# POWER.net
KiCad netlist of a schematic drawn in Altium Designer
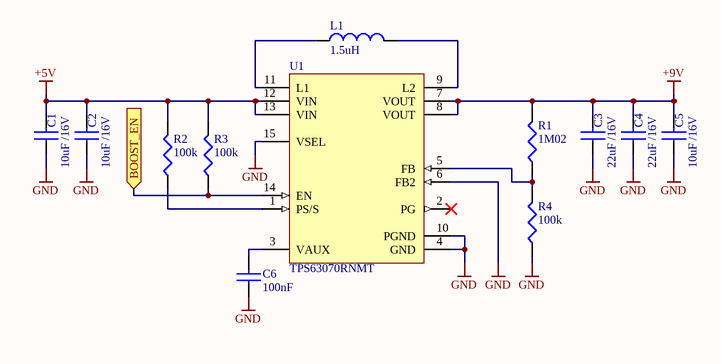
[diagram p0: POWER.SchDoc]

(export (version "E")
  (design (tool "Eeschema 10.0.6"))
  (components
    (comp (ref "C1")
      (value "10uF /16V")
      (footprint "CAP0805")
      (description "TDK - CGA4J1X5R1C106K125AC - CAP, MLCC, X5R, 10UF, 16V, 0805")
      (fields
        (field (name "MANUFACTURER") "TDK")
        (field (name "MANUFACTURER PART NUMBER") "CGA4J1X5R1C106K125AC")
      )
      (libsource (lib "Passive") (part "C - 10uF /16V"))
    )
    (comp (ref "C2")
      (value "10uF /16V")
      (footprint "CAP0805")
      (description "TDK - CGA4J1X5R1C106K125AC - CAP, MLCC, X5R, 10UF, 16V, 0805")
      (fields
        (field (name "MANUFACTURER") "TDK")
        (field (name "MANUFACTURER PART NUMBER") "CGA4J1X5R1C106K125AC")
      )
      (libsource (lib "Passive") (part "C - 10uF /16V"))
    )
    (comp (ref "C3")
      (value "22uF /16V")
      (footprint "CAP0805")
      (description "MULTICOMP - MC0805X226M6R3CT - CAP, MLCC, X5R, 22UF, 0805")
      (fields
        (field (name "MANUFACTURER") "MULTICOMP")
        (field (name "MANUFACTURER PART NUMBER") "MC0805X226M6R3CT")
      )
      (libsource (lib "Passive") (part "C - 22u 6.3V 0805"))
    )
    (comp (ref "C4")
      (value "22uF /16V")
      (footprint "CAP0805")
      (description "MULTICOMP - MC0805X226M6R3CT - CAP, MLCC, X5R, 22UF, 0805")
      (fields
        (field (name "MANUFACTURER") "MULTICOMP")
        (field (name "MANUFACTURER PART NUMBER") "MC0805X226M6R3CT")
      )
      (libsource (lib "Passive") (part "C - 22u 6.3V 0805"))
    )
    (comp (ref "C5")
      (value "10uF /16V")
      (footprint "CAP0805")
      (description "TDK - CGA4J1X5R1C106K125AC - CAP, MLCC, X5R, 10UF, 16V, 0805")
      (fields
        (field (name "MANUFACTURER") "TDK")
        (field (name "MANUFACTURER PART NUMBER") "CGA4J1X5R1C106K125AC")
      )
      (libsource (lib "Passive") (part "C - 10uF /16V"))
    )
    (comp (ref "C6")
      (value "100nF")
      (footprint "CAP0603")
      (description "MURATA - GRM188R71C104KA01J - CAP, MLCC, X7R, 0.1UF, 16V, 0603")
      (fields
        (field (name "MANUFACTURER") "MURATA")
        (field (name "MANUFACTURER PART NUMBER") "GRM188R71C104KA01J")
      )
      (libsource (lib "Passive") (part "C - 100nF"))
    )
    (comp (ref "L1")
      (value "1.5uH")
      (footprint "FDSD0402")
      (description "MURATA - FDSD0420-H-1R5M=P3 - INDUCTOR, SHIELDED, 1.5UH, 5.1A, 20%")
      (fields
        (field (name "MANUFACTURER") "MURATA")
        (field (name "MANUFACTURER PART NUMBER") "FDSD0420-H-1R5M=P3")
      )
      (libsource (lib "Passive") (part "L - 1.5uH 5.1A"))
    )
    (comp (ref "R1")
      (value "1M02")
      (footprint "RES0603")
      (description "MULTICOMP - MCMR06X104 JTL - RES, CERAMIC, 1M02, 1%, 0.1W, 0603")
      (fields
        (field (name "MANUFACTURER") "MULTICOMP")
        (field (name "MANUFACTURER PART NUMBER") "MCMR06X104 JTL")
      )
      (libsource (lib "Passive") (part "R - 100k"))
    )
    (comp (ref "R2")
      (value "100k")
      (footprint "RES0603")
      (description "MULTICOMP - MCMR06X104 JTL - RES, CERAMIC, 100K, 5%, 0.1W, 0603")
      (fields
        (field (name "MANUFACTURER") "MULTICOMP")
        (field (name "MANUFACTURER PART NUMBER") "MCMR06X104 JTL")
      )
      (libsource (lib "Passive") (part "R - 100k"))
    )
    (comp (ref "R3")
      (value "100k")
      (footprint "RES0603")
      (description "MULTICOMP - MCMR06X104 JTL - RES, CERAMIC, 100K, 5%, 0.1W, 0603")
      (fields
        (field (name "MANUFACTURER") "MULTICOMP")
        (field (name "MANUFACTURER PART NUMBER") "MCMR06X104 JTL")
      )
      (libsource (lib "Passive") (part "R - 100k"))
    )
    (comp (ref "R4")
      (value "100k")
      (footprint "RES0603")
      (description "MULTICOMP - MCMR06X104 JTL - RES, CERAMIC, 100K, 1%, 0.1W, 0603")
      (fields
        (field (name "MANUFACTURER") "MULTICOMP")
        (field (name "MANUFACTURER PART NUMBER") "MCMR06X104 JTL")
      )
      (libsource (lib "Passive") (part "R - 100k"))
    )
    (comp (ref "U1")
      (value "TPS63070RNMT")
      (footprint "VQFN TPS")
      (description "TEXAS INSTRUMENTS - TPS63070RNMT - DC/DC CONV, BUCK-BOOST, 2.4MHZ, VQFN-15")
      (fields (field (name "MANUFACTURER") "TEXAS INSTRUMENTS"))
      (libsource (lib "Active") (part "V_SW - TPS63070RNMT"))
    )
  )
  (nets
    (net (code "1") (name "+5V") (class "Default")
      (node (ref "C1") (pin "2") (pinfunction "2_2") (pintype "passive"))
      (node (ref "C2") (pin "2") (pinfunction "2_2") (pintype "passive"))
      (node (ref "R2") (pin "2") (pinfunction "2_2") (pintype "passive"))
      (node (ref "R3") (pin "2") (pinfunction "2_2") (pintype "passive"))
      (node (ref "U1") (pin "12") (pinfunction "VIN_12") (pintype "power_in"))
      (node (ref "U1") (pin "13") (pinfunction "VIN_13") (pintype "power_in"))
    )
    (net (code "2") (name "+9V") (class "Default")
      (node (ref "C3") (pin "2") (pinfunction "2_2") (pintype "passive"))
      (node (ref "C4") (pin "2") (pinfunction "2_2") (pintype "passive"))
      (node (ref "C5") (pin "2") (pinfunction "2_2") (pintype "passive"))
      (node (ref "R1") (pin "2") (pinfunction "2_2") (pintype "passive"))
      (node (ref "U1") (pin "7") (pinfunction "VOUT_7") (pintype "power_in"))
      (node (ref "U1") (pin "8") (pinfunction "VOUT_8") (pintype "power_in"))
    )
    (net (code "3") (name "/BOOST_EN") (class "Default")
      (node (ref "R3") (pin "1") (pinfunction "1_1") (pintype "passive"))
      (node (ref "U1") (pin "14") (pinfunction "EN_14") (pintype "input"))
    )
    (net (code "4") (name "GND") (class "Default")
      (node (ref "C1") (pin "1") (pinfunction "1_1") (pintype "passive"))
      (node (ref "C2") (pin "1") (pinfunction "1_1") (pintype "passive"))
      (node (ref "C3") (pin "1") (pinfunction "1_1") (pintype "passive"))
      (node (ref "C4") (pin "1") (pinfunction "1_1") (pintype "passive"))
      (node (ref "C5") (pin "1") (pinfunction "1_1") (pintype "passive"))
      (node (ref "C6") (pin "1") (pinfunction "1_1") (pintype "passive"))
      (node (ref "R4") (pin "1") (pinfunction "1_1") (pintype "passive"))
      (node (ref "U1") (pin "10") (pinfunction "PGND_10") (pintype "power_in"))
      (node (ref "U1") (pin "15") (pinfunction "VSEL_15") (pintype "power_in"))
      (node (ref "U1") (pin "4") (pinfunction "GND_4") (pintype "power_in"))
      (node (ref "U1") (pin "6") (pinfunction "FB2_6") (pintype "input"))
    )
    (net (code "5") (name "Net-(U1-FB)") (class "Default")
      (node (ref "R1") (pin "1") (pinfunction "1_1") (pintype "passive"))
      (node (ref "R4") (pin "2") (pinfunction "2_2") (pintype "passive"))
      (node (ref "U1") (pin "5") (pinfunction "FB_5") (pintype "input"))
    )
    (net (code "6") (name "Net-(U1-L1)") (class "Default")
      (node (ref "L1") (pin "1") (pinfunction "1_1") (pintype "passive"))
      (node (ref "U1") (pin "11") (pinfunction "L1_11") (pintype "power_in"))
    )
    (net (code "7") (name "Net-(U1-L2)") (class "Default")
      (node (ref "L1") (pin "2") (pinfunction "2_2") (pintype "passive"))
      (node (ref "U1") (pin "9") (pinfunction "L2_9") (pintype "power_in"))
    )
    (net (code "8") (name "Net-(U1-PS{slash}S)") (class "Default")
      (node (ref "R2") (pin "1") (pinfunction "1_1") (pintype "passive"))
      (node (ref "U1") (pin "1") (pinfunction "PS/S_1") (pintype "input"))
    )
    (net (code "9") (name "Net-(U1-VAUX)") (class "Default")
      (node (ref "C6") (pin "2") (pinfunction "2_2") (pintype "passive"))
      (node (ref "U1") (pin "3") (pinfunction "VAUX_3") (pintype "power_in"))
    )
    (net (code "10") (name "unconnected-(U1-PG-Pad2)") (class "Default")
      (node (ref "U1") (pin "2") (pinfunction "PG_2") (pintype "output+no_connect"))
    )
  )
)
